# DC_Motor_Driver.net
KiCad netlist of a schematic drawn in Altium Designer
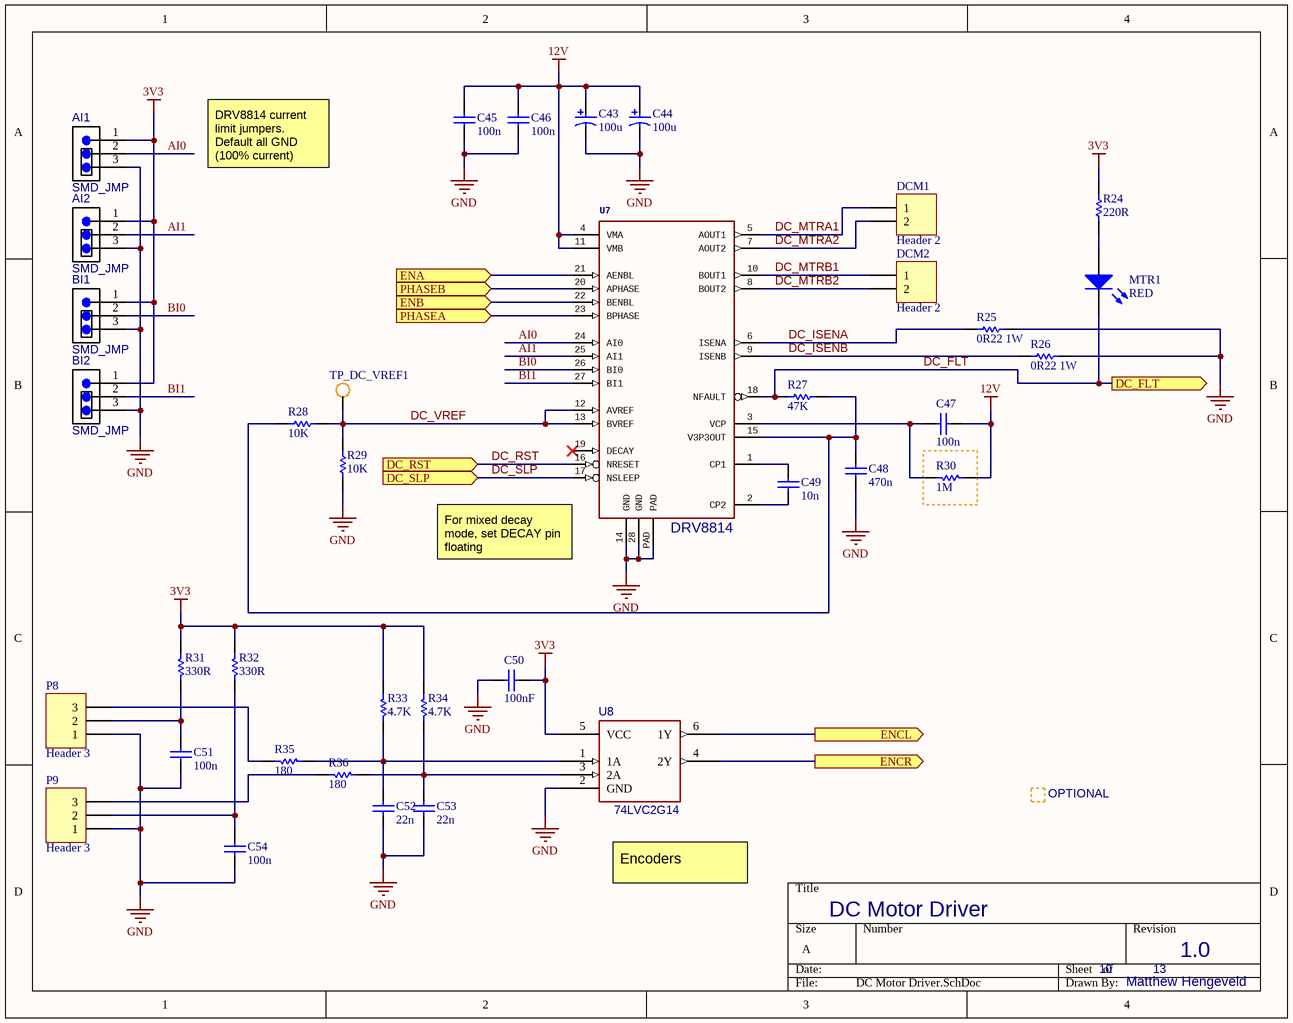
[diagram p0: DC Motor Driver.SchDoc]

(export (version "E")
  (design (tool "Eeschema 10.0.6"))
  (components
    (comp (ref "AI1")
      (value "SMD_JMP")
      (footprint "0603_JUMPER")
      (libsource (lib "Hengeveld") (part "SMD_JMP"))
    )
    (comp (ref "AI2")
      (value "SMD_JMP")
      (footprint "0603_JUMPER")
      (libsource (lib "Hengeveld") (part "SMD_JMP"))
    )
    (comp (ref "BI1")
      (value "SMD_JMP")
      (footprint "0603_JUMPER")
      (libsource (lib "Hengeveld") (part "SMD_JMP"))
    )
    (comp (ref "BI2")
      (value "SMD_JMP")
      (footprint "0603_JUMPER")
      (libsource (lib "Hengeveld") (part "SMD_JMP"))
    )
    (comp (ref "C43")
      (value "100u")
      (footprint "SMD-CAP-0606")
      (fields (field (name "PARTNUMBER") "UUD1V101MNL1GS") (field (name "MANUFACTURER") "Nichicon"))
      (libsource (lib "Hengeveld") (part "CAP-EL-0606-SMD"))
    )
    (comp (ref "C44")
      (value "100u")
      (footprint "SMD-CAP-0606")
      (fields (field (name "PARTNUMBER") "UUD1V101MNL1GS") (field (name "MANUFACTURER") "Nichicon"))
      (libsource (lib "Hengeveld") (part "CAP-EL-0606-SMD"))
    )
    (comp (ref "C45")
      (value "100n")
      (footprint "CAPC1608X87X35LL15T15")
      (fields (field (name "PART NUMBER") "C0603X104K5RACTU") (field (name "MANUFACTURER") "Kemet"))
      (libsource (lib "Altium Content Vault") (part "CAP"))
    )
    (comp (ref "C46")
      (value "100n")
      (footprint "CAPC1608X87X35LL15T15")
      (fields (field (name "PART NUMBER") "C0603X104K5RACTU") (field (name "MANUFACTURER") "Kemet"))
      (libsource (lib "Altium Content Vault") (part "CAP"))
    )
    (comp (ref "C47")
      (value "100n")
      (footprint "CAPC1608X87X35LL15T15")
      (fields (field (name "PART NUMBER") "C0603X104K5RACTU") (field (name "MANUFACTURER") "Kemet"))
      (libsource (lib "Altium Content Vault") (part "CAP"))
    )
    (comp (ref "C48")
      (value "470n")
      (footprint "CAPC1608X90X35LL10T15")
      (fields (field (name "MANUFACTURER") "Murata") (field (name "PART NUMBER") "GRM188R71C474KA88D"))
      (libsource (lib "Altium Content Vault") (part "CAP"))
    )
    (comp (ref "C49")
      (value "10n")
      (footprint "CAPC1608X87X35LL15T15")
      (fields (field (name "MANUFACTURER") "Kemet") (field (name "PART NUMBER") "C0603C103K1RACTU"))
      (libsource (lib "Altium Content Vault") (part "CAP"))
    )
    (comp (ref "C50")
      (value "100nF")
      (footprint "CAPC1608X92X38LL15T08")
      (fields (field (name "PART NUMBER") "VJ0603Y104KNXAO") (field (name "MANUFACTURER") "Vitramon"))
      (libsource (lib "Altium Content Vault") (part "CAP"))
    )
    (comp (ref "C51")
      (value "100n")
      (footprint "CAPC1608X87X35LL15T15")
      (fields (field (name "PART NUMBER") "C0603X104K5RACTU") (field (name "MANUFACTURER") "Kemet"))
      (libsource (lib "Altium Content Vault") (part "CAP"))
    )
    (comp (ref "C52")
      (value "22n")
      (footprint "CAPC1608X87X35LL15T15")
      (fields (field (name "PART NUMBER") "C0603X104K5RACTU") (field (name "MANUFACTURER") "Kemet"))
      (libsource (lib "Altium Content Vault") (part "CAP"))
    )
    (comp (ref "C53")
      (value "22n")
      (footprint "CAPC1608X87X35LL15T15")
      (fields (field (name "PART NUMBER") "C0603X104K5RACTU") (field (name "MANUFACTURER") "Kemet"))
      (libsource (lib "Altium Content Vault") (part "CAP"))
    )
    (comp (ref "C54")
      (value "100n")
      (footprint "CAPC1608X87X35LL15T15")
      (fields (field (name "PART NUMBER") "C0603X104K5RACTU") (field (name "MANUFACTURER") "Kemet"))
      (libsource (lib "Altium Content Vault") (part "CAP"))
    )
    (comp (ref "DCM1")
      (value "Header 2")
      (footprint "HDR1X2")
      (description "Header, 2-Pin")
      (fields (field (name "PUBLISHER") "Altium Limited"))
      (libsource (lib "Hengeveld") (part "Header 2"))
    )
    (comp (ref "DCM2")
      (value "Header 2")
      (footprint "HDR1X2")
      (description "Header, 2-Pin")
      (fields (field (name "PUBLISHER") "Altium Limited"))
      (libsource (lib "Hengeveld") (part "Header 2"))
    )
    (comp (ref "MTR1")
      (value "RED")
      (footprint "0805_A")
      (description "SMD mono-color Chip LED, WL-SMCW, Red")
      (fields (field (name "PARTNUMBER") "150080RS75000") (field (name "MANUFACTURER") "Wuerth Elektronik"))
      (libsource (lib "Altium Content Vault") (part "WE-LED_K1A2-2"))
    )
    (comp (ref "P8")
      (value "Header 3")
      (footprint "HDR1X3")
      (description "Header, 3-Pin")
      (fields (field (name "PUBLISHER") "Altium Limited"))
      (libsource (lib "Hengeveld") (part "Header 3"))
    )
    (comp (ref "P9")
      (value "Header 3")
      (footprint "HDR1X3")
      (description "Header, 3-Pin")
      (fields (field (name "PUBLISHER") "Altium Limited"))
      (libsource (lib "Hengeveld") (part "Header 3"))
    )
    (comp (ref "R24")
      (value "220R")
      (footprint "RESC1608X55X30LL15T15")
      (fields (field (name "MANUFACTURER") "Panasonic") (field (name "PART NUMBER") "ERJ-3GEYJ103V"))
      (libsource (lib "Altium Content Vault") (part "RES"))
    )
    (comp (ref "R25")
      (value "0R22 1W")
      (footprint "ROHM-MCR100-2_V")
      (description "Low Ohmic Thick Film Chip Resistor, 0.47 Ohm, -55 to 125 degC, 2-Pin SMD, RoHS, Tape")
      (fields
        (field (name "PARTNUMBER") "MCR100JZHFLR470")
        (field (name "MANUFACTURER") "ROHM Semiconductor")
      )
      (libsource (lib "Altium Content Vault") (part "ROHM-RES-2"))
    )
    (comp (ref "R26")
      (value "0R22 1W")
      (footprint "ROHM-MCR100-2_V")
      (description "Low Ohmic Thick Film Chip Resistor, 0.47 Ohm, -55 to 125 degC, 2-Pin SMD, RoHS, Tape")
      (fields
        (field (name "PARTNUMBER") "MCR100JZHFLR470")
        (field (name "MANUFACTURER") "ROHM Semiconductor")
      )
      (libsource (lib "Altium Content Vault") (part "ROHM-RES-2"))
    )
    (comp (ref "R27")
      (value "47K")
      (footprint "RESC1608X55X30LL15T15")
      (fields (field (name "MANUFACTURER") "Panasonic") (field (name "PART NUMBER") "ERJ-3GEYJ103V"))
      (libsource (lib "Altium Content Vault") (part "RES"))
    )
    (comp (ref "R28")
      (value "10K")
      (footprint "RESC1608X55X30LL15T15")
      (fields (field (name "MANUFACTURER") "Panasonic") (field (name "PART NUMBER") "ERJ-3GEYJ103V"))
      (libsource (lib "Altium Content Vault") (part "RES"))
    )
    (comp (ref "R29")
      (value "10K")
      (footprint "RESC1608X55X30LL15T15")
      (fields (field (name "MANUFACTURER") "Panasonic") (field (name "PART NUMBER") "ERJ-3GEYJ103V"))
      (libsource (lib "Altium Content Vault") (part "RES"))
    )
    (comp (ref "R30")
      (value "1M")
      (footprint "RESC1608X55X30LL15T15")
      (fields (field (name "MANUFACTURER") "Panasonic") (field (name "PART NUMBER") "ERJ-3GEYJ103V"))
      (libsource (lib "Altium Content Vault") (part "RES"))
    )
    (comp (ref "R31")
      (value "330R")
      (footprint "RESC1608X55X30LL15T15")
      (fields (field (name "MANUFACTURER") "Panasonic") (field (name "PART NUMBER") "ERJ-3GEYJ103V"))
      (libsource (lib "Altium Content Vault") (part "RES"))
    )
    (comp (ref "R32")
      (value "330R")
      (footprint "RESC1608X55X30LL15T15")
      (fields (field (name "MANUFACTURER") "Panasonic") (field (name "PART NUMBER") "ERJ-3GEYJ103V"))
      (libsource (lib "Altium Content Vault") (part "RES"))
    )
    (comp (ref "R33")
      (value "4.7K")
      (footprint "RESC1608X55X30LL15T15")
      (fields (field (name "MANUFACTURER") "Panasonic") (field (name "PART NUMBER") "ERJ-3GEYJ103V"))
      (libsource (lib "Altium Content Vault") (part "RES"))
    )
    (comp (ref "R34")
      (value "4.7K")
      (footprint "RESC1608X55X30LL15T15")
      (fields (field (name "MANUFACTURER") "Panasonic") (field (name "PART NUMBER") "ERJ-3GEYJ103V"))
      (libsource (lib "Altium Content Vault") (part "RES"))
    )
    (comp (ref "R35")
      (value "180")
      (footprint "RESC1608X55X30LL15T15")
      (fields (field (name "MANUFACTURER") "Panasonic") (field (name "PART NUMBER") "ERJ-3GEYJ103V"))
      (libsource (lib "Altium Content Vault") (part "RES"))
    )
    (comp (ref "R36")
      (value "180")
      (footprint "RESC1608X55X30LL15T15")
      (fields (field (name "MANUFACTURER") "Panasonic") (field (name "PART NUMBER") "ERJ-3GEYJ103V"))
      (libsource (lib "Altium Content Vault") (part "RES"))
    )
    (comp (ref "TP_DC_VREF1")
      (value "Test point")
      (footprint "SMD Test Hook")
      (libsource (lib "Hengeveld") (part "Test Point"))
    )
    (comp (ref "U7") (value "DRV8814") (footprint "TI-PWP28") (libsource (lib "Hengeveld") (part "DRV8814")))
    (comp (ref "U8")
      (value "74LVC2G14")
      (footprint "ONSC-SOT-363-6-419B-02_V")
      (libsource (lib "Hengeveld") (part "74LVC2G14"))
    )
  )
  (nets
    (net (code "1") (name "/AI0") (class "Default")
      (node (ref "AI1") (pin "2") (pinfunction "2_2") (pintype "passive"))
      (node (ref "U7") (pin "24") (pinfunction "AI0_24") (pintype "input"))
    )
    (net (code "2") (name "/AI1") (class "Default")
      (node (ref "AI2") (pin "2") (pinfunction "2_2") (pintype "passive"))
      (node (ref "U7") (pin "25") (pinfunction "AI1_25") (pintype "input"))
    )
    (net (code "3") (name "/BI0") (class "Default")
      (node (ref "BI1") (pin "2") (pinfunction "2_2") (pintype "passive"))
      (node (ref "U7") (pin "26") (pinfunction "BI0_26") (pintype "input"))
    )
    (net (code "4") (name "/BI1") (class "Default")
      (node (ref "BI2") (pin "2") (pinfunction "2_2") (pintype "passive"))
      (node (ref "U7") (pin "27") (pinfunction "BI1_27") (pintype "input"))
    )
    (net (code "5") (name "/DC_FLT") (class "Default")
      (node (ref "MTR1") (pin "1") (pinfunction "K_1") (pintype "passive"))
      (node (ref "R27") (pin "2") (pinfunction "2_2") (pintype "passive"))
      (node (ref "U7") (pin "18") (pinfunction "NFAULT_18") (pintype "output"))
    )
    (net (code "6") (name "/DC_ISENA") (class "Default")
      (node (ref "R25") (pin "1") (pinfunction "1_1") (pintype "passive"))
      (node (ref "U7") (pin "6") (pinfunction "ISENA_6") (pintype "output"))
    )
    (net (code "7") (name "/DC_ISENB") (class "Default")
      (node (ref "R26") (pin "1") (pinfunction "1_1") (pintype "passive"))
      (node (ref "U7") (pin "9") (pinfunction "ISENB_9") (pintype "output"))
    )
    (net (code "8") (name "/DC_MTRA1") (class "Default")
      (node (ref "DCM1") (pin "1") (pinfunction "1_1") (pintype "passive"))
      (node (ref "U7") (pin "5") (pinfunction "AOUT1_5") (pintype "output"))
    )
    (net (code "9") (name "/DC_MTRA2") (class "Default")
      (node (ref "DCM1") (pin "2") (pinfunction "2_2") (pintype "passive"))
      (node (ref "U7") (pin "7") (pinfunction "AOUT2_7") (pintype "output"))
    )
    (net (code "10") (name "/DC_MTRB1") (class "Default")
      (node (ref "DCM2") (pin "1") (pinfunction "1_1") (pintype "passive"))
      (node (ref "U7") (pin "10") (pinfunction "BOUT1_10") (pintype "output"))
    )
    (net (code "11") (name "/DC_MTRB2") (class "Default")
      (node (ref "DCM2") (pin "2") (pinfunction "2_2") (pintype "passive"))
      (node (ref "U7") (pin "8") (pinfunction "BOUT2_8") (pintype "output"))
    )
    (net (code "12") (name "/DC_RST") (class "Default")
      (node (ref "U7") (pin "16") (pinfunction "NRESET_16") (pintype "input"))
    )
    (net (code "13") (name "/DC_SLP") (class "Default")
      (node (ref "U7") (pin "17") (pinfunction "NSLEEP_17") (pintype "input"))
    )
    (net (code "14") (name "/DC_VREF") (class "Default")
      (node (ref "R28") (pin "1") (pinfunction "1_1") (pintype "passive"))
      (node (ref "R29") (pin "2") (pinfunction "2_2") (pintype "passive"))
      (node (ref "TP_DC_VREF1") (pin "1") (pinfunction "point_1") (pintype "passive"))
      (node (ref "U7") (pin "12") (pinfunction "AVREF_12") (pintype "input"))
      (node (ref "U7") (pin "13") (pinfunction "BVREF_13") (pintype "input"))
    )
    (net (code "15") (name "/ENA") (class "Default")
      (node (ref "U7") (pin "21") (pinfunction "AENBL_21") (pintype "input"))
    )
    (net (code "16") (name "/ENB") (class "Default")
      (node (ref "U7") (pin "22") (pinfunction "BENBL_22") (pintype "input"))
    )
    (net (code "17") (name "/ENCL") (class "Default")
      (node (ref "U8") (pin "6") (pinfunction "1Y_6") (pintype "output"))
    )
    (net (code "18") (name "/ENCR") (class "Default")
      (node (ref "U8") (pin "4") (pinfunction "2Y_4") (pintype "output"))
    )
    (net (code "19") (name "/PHASEA") (class "Default")
      (node (ref "U7") (pin "23") (pinfunction "BPHASE_23") (pintype "input"))
    )
    (net (code "20") (name "/PHASEB") (class "Default")
      (node (ref "U7") (pin "20") (pinfunction "APHASE_20") (pintype "input"))
    )
    (net (code "21") (name "3V3") (class "Default")
      (node (ref "AI1") (pin "1") (pinfunction "1_1") (pintype "passive"))
      (node (ref "AI2") (pin "1") (pinfunction "1_1") (pintype "passive"))
      (node (ref "BI1") (pin "1") (pinfunction "1_1") (pintype "passive"))
      (node (ref "BI2") (pin "1") (pinfunction "1_1") (pintype "passive"))
      (node (ref "C50") (pin "2") (pinfunction "2_2") (pintype "passive"))
      (node (ref "R24") (pin "1") (pinfunction "1_1") (pintype "passive"))
      (node (ref "R31") (pin "2") (pinfunction "2_2") (pintype "passive"))
      (node (ref "R32") (pin "2") (pinfunction "2_2") (pintype "passive"))
      (node (ref "R33") (pin "1") (pinfunction "1_1") (pintype "passive"))
      (node (ref "R34") (pin "1") (pinfunction "1_1") (pintype "passive"))
      (node (ref "U8") (pin "5") (pinfunction "VCC_5") (pintype "power_in"))
    )
    (net (code "22") (name "12V") (class "Default")
      (node (ref "C43") (pin "1") (pinfunction "1_1") (pintype "passive"))
      (node (ref "C44") (pin "1") (pinfunction "1_1") (pintype "passive"))
      (node (ref "C45") (pin "2") (pinfunction "2_2") (pintype "passive"))
      (node (ref "C46") (pin "2") (pinfunction "2_2") (pintype "passive"))
      (node (ref "C47") (pin "1") (pinfunction "1_1") (pintype "passive"))
      (node (ref "R30") (pin "1") (pinfunction "1_1") (pintype "passive"))
      (node (ref "U7") (pin "11") (pinfunction "VMB_11") (pintype "power_in"))
      (node (ref "U7") (pin "4") (pinfunction "VMA_4") (pintype "power_in"))
    )
    (net (code "23") (name "GND") (class "Default")
      (node (ref "AI1") (pin "3") (pinfunction "3_3") (pintype "passive"))
      (node (ref "AI2") (pin "3") (pinfunction "3_3") (pintype "passive"))
      (node (ref "BI1") (pin "3") (pinfunction "3_3") (pintype "passive"))
      (node (ref "BI2") (pin "3") (pinfunction "3_3") (pintype "passive"))
      (node (ref "C43") (pin "2") (pinfunction "2_2") (pintype "passive"))
      (node (ref "C44") (pin "2") (pinfunction "2_2") (pintype "passive"))
      (node (ref "C45") (pin "1") (pinfunction "1_1") (pintype "passive"))
      (node (ref "C46") (pin "1") (pinfunction "1_1") (pintype "passive"))
      (node (ref "C48") (pin "1") (pinfunction "1_1") (pintype "passive"))
      (node (ref "C50") (pin "1") (pinfunction "1_1") (pintype "passive"))
      (node (ref "C51") (pin "2") (pinfunction "2_2") (pintype "passive"))
      (node (ref "C52") (pin "2") (pinfunction "2_2") (pintype "passive"))
      (node (ref "C53") (pin "2") (pinfunction "2_2") (pintype "passive"))
      (node (ref "C54") (pin "2") (pinfunction "2_2") (pintype "passive"))
      (node (ref "P8") (pin "1") (pinfunction "1_1") (pintype "passive"))
      (node (ref "P9") (pin "1") (pinfunction "1_1") (pintype "passive"))
      (node (ref "R25") (pin "2") (pinfunction "2_2") (pintype "passive"))
      (node (ref "R26") (pin "2") (pinfunction "2_2") (pintype "passive"))
      (node (ref "R29") (pin "1") (pinfunction "1_1") (pintype "passive"))
      (node (ref "U7") (pin "14") (pinfunction "GND_14") (pintype "power_in"))
      (node (ref "U7") (pin "28") (pinfunction "GND_28") (pintype "power_in"))
      (node (ref "U7") (pin "PAD") (pinfunction "PAD_PAD") (pintype "power_in"))
      (node (ref "U8") (pin "2") (pinfunction "GND_2") (pintype "power_in"))
    )
    (net (code "24") (name "Net-(C51-Pad1)") (class "Default")
      (node (ref "C51") (pin "1") (pinfunction "1_1") (pintype "passive"))
      (node (ref "P8") (pin "2") (pinfunction "2_2") (pintype "passive"))
      (node (ref "R31") (pin "1") (pinfunction "1_1") (pintype "passive"))
    )
    (net (code "25") (name "Net-(C54-Pad1)") (class "Default")
      (node (ref "C54") (pin "1") (pinfunction "1_1") (pintype "passive"))
      (node (ref "P9") (pin "2") (pinfunction "2_2") (pintype "passive"))
      (node (ref "R32") (pin "1") (pinfunction "1_1") (pintype "passive"))
    )
    (net (code "26") (name "Net-(MTR1-A)") (class "Default")
      (node (ref "MTR1") (pin "2") (pinfunction "A_2") (pintype "passive"))
      (node (ref "R24") (pin "2") (pinfunction "2_2") (pintype "passive"))
    )
    (net (code "27") (name "Net-(P8-Pad3)") (class "Default")
      (node (ref "P8") (pin "3") (pinfunction "3_3") (pintype "passive"))
      (node (ref "R35") (pin "2") (pinfunction "2_2") (pintype "passive"))
    )
    (net (code "28") (name "Net-(P9-Pad3)") (class "Default")
      (node (ref "P9") (pin "3") (pinfunction "3_3") (pintype "passive"))
      (node (ref "R36") (pin "2") (pinfunction "2_2") (pintype "passive"))
    )
    (net (code "29") (name "Net-(U7-CP1)") (class "Default")
      (node (ref "C49") (pin "2") (pinfunction "2_2") (pintype "passive"))
      (node (ref "U7") (pin "1") (pinfunction "CP1_1") (pintype "power_in"))
    )
    (net (code "30") (name "Net-(U7-CP2)") (class "Default")
      (node (ref "C49") (pin "1") (pinfunction "1_1") (pintype "passive"))
      (node (ref "U7") (pin "2") (pinfunction "CP2_2") (pintype "power_in"))
    )
    (net (code "31") (name "Net-(U7-V3P3OUT)") (class "Default")
      (node (ref "C48") (pin "2") (pinfunction "2_2") (pintype "passive"))
      (node (ref "R27") (pin "1") (pinfunction "1_1") (pintype "passive"))
      (node (ref "R28") (pin "2") (pinfunction "2_2") (pintype "passive"))
      (node (ref "U7") (pin "15") (pinfunction "V3P3OUT_15") (pintype "power_in"))
    )
    (net (code "32") (name "Net-(U7-VCP)") (class "Default")
      (node (ref "C47") (pin "2") (pinfunction "2_2") (pintype "passive"))
      (node (ref "R30") (pin "2") (pinfunction "2_2") (pintype "passive"))
      (node (ref "U7") (pin "3") (pinfunction "VCP_3") (pintype "power_in"))
    )
    (net (code "33") (name "Net-(U8-1A)") (class "Default")
      (node (ref "C52") (pin "1") (pinfunction "1_1") (pintype "passive"))
      (node (ref "R33") (pin "2") (pinfunction "2_2") (pintype "passive"))
      (node (ref "R35") (pin "1") (pinfunction "1_1") (pintype "passive"))
      (node (ref "U8") (pin "1") (pinfunction "1A_1") (pintype "input"))
    )
    (net (code "34") (name "Net-(U8-2A)") (class "Default")
      (node (ref "C53") (pin "1") (pinfunction "1_1") (pintype "passive"))
      (node (ref "R34") (pin "2") (pinfunction "2_2") (pintype "passive"))
      (node (ref "R36") (pin "1") (pinfunction "1_1") (pintype "passive"))
      (node (ref "U8") (pin "3") (pinfunction "2A_3") (pintype "input"))
    )
    (net (code "35") (name "unconnected-(U7-DECAY-Pad19)") (class "Default")
      (node (ref "U7") (pin "19") (pinfunction "DECAY_19") (pintype "input+no_connect"))
    )
  )
)
